# MCU_and_Antenna.net
KiCad netlist of a schematic drawn in Altium Designer
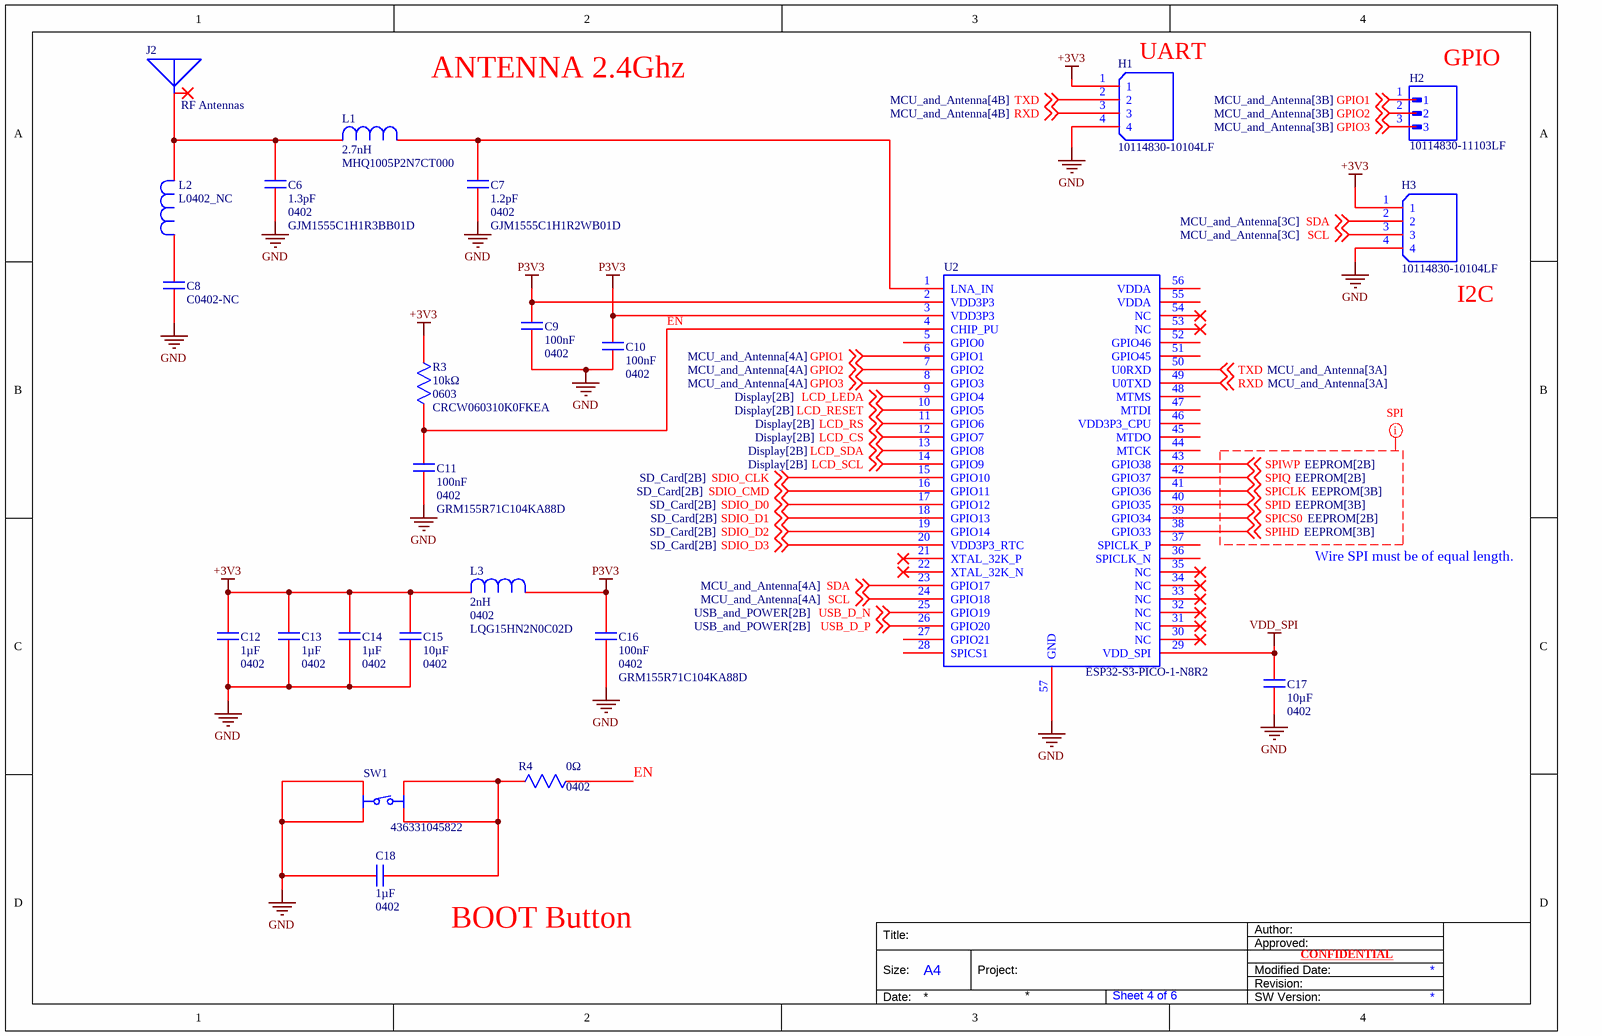
[diagram p0: MCU_and_Antenna.SchDoc]

(export (version "E")
  (design (tool "Eeschema 10.0.6"))
  (components
    (comp (ref "C6")
      (value "GJM1555C1H1R3BB01D")
      (footprint "CAPC1005X55N")
      (description "50V 1.3pF C0G 0402 Multilayer Ceramic Capacitors MLCC - SMD/SMT ROHS")
      (fields
        (field (name "MANUFACTURER") "Murata")
        (field (name "LCSC PART") "C161309")
        (field (name "CASE CODE (IMPERIAL)") "0402")
        (field (name "ALTIUM_VALUE") "1.3pF")
      )
      (libsource (lib "Schlib") (part "GJM1555C1H1R3BB01D"))
    )
    (comp (ref "C7")
      (value "GJM1555C1H1R2WB01D")
      (footprint "CAPC1005X55N")
      (description "50V 1.2pF C0G 0402 Multilayer Ceramic Capacitors MLCC - SMD/SMT ROHS")
      (fields
        (field (name "MANUFACTURER") "Murata")
        (field (name "VOLTAGE") "50V")
        (field (name "CASE/PACKAGE") "0402")
        (field (name "ALTIUM_VALUE") "1.2pF")
      )
      (libsource (lib "Schlib") (part "GJM1555C1H1R2WB01D"))
    )
    (comp (ref "C8")
      (value "C0402-NC")
      (footprint "CAPC1005X55N - NC")
      (libsource (lib "Schlib") (part "C0402-NC"))
    )
    (comp (ref "C9")
      (value "100nF")
      (footprint "CAPC1005X55N")
      (description "16V 100nF X7R ±10% 0402 Multilayer Ceramic Capacitors MLCC - SMD/SMT ROHS")
      (fields
        (field (name "MANUFACTURER") "Murata")
        (field (name "MANUFACTURER PART NUMBER") "GRM155R71C104KA88D")
        (field (name "CASE/PACKAGE") "0402")
      )
      (libsource (lib "Schlib") (part "GRM155R71C104KA88D"))
    )
    (comp (ref "C10")
      (value "100nF")
      (footprint "CAPC1005X55N")
      (description "16V 100nF X7R ±10% 0402 Multilayer Ceramic Capacitors MLCC - SMD/SMT ROHS")
      (fields
        (field (name "MANUFACTURER") "Murata")
        (field (name "MANUFACTURER PART NUMBER") "GRM155R71C104KA88D")
        (field (name "CASE/PACKAGE") "0402")
      )
      (libsource (lib "Schlib") (part "GRM155R71C104KA88D"))
    )
    (comp (ref "C11")
      (value "GRM155R71C104KA88D")
      (footprint "CAPC1005X55N")
      (description "16V 100nF X7R ±10% 0402 Multilayer Ceramic Capacitors MLCC - SMD/SMT ROHS")
      (fields
        (field (name "MANUFACTURER") "Murata")
        (field (name "TOLERANCE") "10%")
        (field (name "CASE/PACKAGE") "0402")
        (field (name "ALTIUM_VALUE") "100nF")
      )
      (libsource (lib "Schlib") (part "GRM155R71C104KA88D"))
    )
    (comp (ref "C12")
      (value "1µF")
      (footprint "CAPC1005X55N")
      (description "10V 1uF X5R 卤10% 0402 Multilayer Ceramic Capacitors MLCC - SMD/SMT ROHS")
      (fields
        (field (name "MANUFACTURER") "Samsung Electro-Mechanics")
        (field (name "MANUFACTURER PART NUMBER") "CL05A105KP5NNNC")
        (field (name "CASE/PACKAGE") "0402")
      )
      (libsource (lib "Schlib") (part "CL05A105KP5NNNC"))
    )
    (comp (ref "C13")
      (value "1µF")
      (footprint "CAPC1005X55N")
      (description "10V 1uF X5R 卤10% 0402 Multilayer Ceramic Capacitors MLCC - SMD/SMT ROHS")
      (fields
        (field (name "MANUFACTURER") "Samsung Electro-Mechanics")
        (field (name "MANUFACTURER PART NUMBER") "CL05A105KP5NNNC")
        (field (name "CASE/PACKAGE") "0402")
      )
      (libsource (lib "Schlib") (part "CL05A105KP5NNNC"))
    )
    (comp (ref "C14")
      (value "1µF")
      (footprint "CAPC1005X55N")
      (description "10V 1uF X5R 卤10% 0402 Multilayer Ceramic Capacitors MLCC - SMD/SMT ROHS")
      (fields
        (field (name "MANUFACTURER") "Samsung Electro-Mechanics")
        (field (name "MANUFACTURER PART NUMBER") "CL05A105KP5NNNC")
        (field (name "CASE/PACKAGE") "0402")
      )
      (libsource (lib "Schlib") (part "CL05A105KP5NNNC"))
    )
    (comp (ref "C15")
      (value "10µF")
      (footprint "CAPC1005X55N")
      (description "6.3V 10uF X5R ±20% 0402 Multilayer Ceramic Capacitors MLCC - SMD/SMT ROHS")
      (fields
        (field (name "MANUFACTURER") "Murata")
        (field (name "MANUFACTURER PART NUMBER") "GRM155R60J106ME15D")
        (field (name "CASE/PACKAGE") "0402")
      )
      (libsource (lib "Schlib") (part "GRM155R60J106ME15D"))
    )
    (comp (ref "C16")
      (value "GRM155R71C104KA88D")
      (footprint "CAPC1005X55N")
      (description "16V 100nF X7R ±10% 0402 Multilayer Ceramic Capacitors MLCC - SMD/SMT ROHS")
      (fields
        (field (name "MANUFACTURER") "Murata")
        (field (name "TOLERANCE") "10%")
        (field (name "CASE/PACKAGE") "0402")
        (field (name "ALTIUM_VALUE") "100nF")
      )
      (libsource (lib "Schlib") (part "GRM155R71C104KA88D"))
    )
    (comp (ref "C17")
      (value "10µF")
      (footprint "CAPC1005X55N")
      (description "6.3V 10uF X5R ±20% 0402 Multilayer Ceramic Capacitors MLCC - SMD/SMT ROHS")
      (fields
        (field (name "MANUFACTURER") "Murata")
        (field (name "MANUFACTURER PART NUMBER") "GRM155R60J106ME15D")
        (field (name "CASE/PACKAGE") "0402")
      )
      (libsource (lib "Schlib") (part "GRM155R60J106ME15D"))
    )
    (comp (ref "C18")
      (value "1µF")
      (footprint "CAPC1005X55N")
      (description "10V 1uF X5R 卤10% 0402 Multilayer Ceramic Capacitors MLCC - SMD/SMT ROHS")
      (fields
        (field (name "MANUFACTURER") "Samsung Electro-Mechanics")
        (field (name "MANUFACTURER PART NUMBER") "CL05A105KP5NNNC")
        (field (name "CASE/PACKAGE") "0402")
      )
      (libsource (lib "Schlib") (part "CL05A105KP5NNNC"))
    )
    (comp (ref "H1")
      (value "10114830-10104LF")
      (footprint "AMPHENOL_10114830-10104LF")
      (description "Board Connector, 4 Contact(S), 1 Row(S), Male, Right Angle, 0.049 Inch Pitch, Surface Mount")
      (fields
        (field (name "MANUFACTURER") "Amphenol Communications Solutions")
        (field (name "LCSC PART") "C5407185")
      )
      (libsource (lib "Schlib") (part "10114830-10104LF"))
    )
    (comp (ref "H2")
      (value "10114830-11103LF")
      (footprint "AMPHENOL_10114830-11103LF")
      (description "WTB 1.25 WAFER 90 SMT-10114830-11103LF ¦ Amphenol FCI (Amphenol CS) 1011483011103LF")
      (fields
        (field (name "MANUFACTURER") "Amphenol Communications Solutions")
        (field (name "LCSC PART") "C5407064")
      )
      (libsource (lib "Schlib") (part "10114830-11103LF"))
    )
    (comp (ref "H3")
      (value "10114830-10104LF")
      (footprint "AMPHENOL_10114830-10104LF")
      (description "Board Connector, 4 Contact(S), 1 Row(S), Male, Right Angle, 0.049 Inch Pitch, Surface Mount")
      (fields
        (field (name "MANUFACTURER") "Amphenol Communications Solutions")
        (field (name "LCSC PART") "C5407185")
      )
      (libsource (lib "Schlib") (part "10114830-10104LF"))
    )
    (comp (ref "J2")
      (value "RF Antennas")
      (footprint "ANT3216LL00R2400A")
      (description "CERAMIC HELIX CHIP ANTENNA, 433MHZ, 1204; Available until stocks are exhausted")
      (fields
        (field (name "MANUFACTURER") "Yageo Group")
        (field (name "MANUFACTURER PART NUMBER") "ANT3216LL00R2400A")
      )
      (libsource (lib "Schlib") (part "ANT3216LL00R2400A"))
    )
    (comp (ref "L1")
      (value "MHQ1005P2N7CT000")
      (footprint "IND_1005_TDK")
      (description "General Purpose Inductor, 0.0027uH, 7.4074%, 1 Element, Ceramic-Core, SMD, 0402")
      (fields
        (field (name "MANUFACTURER") "TDK")
        (field (name "TOLERANCE") "0.07%")
        (field (name "ALTIUM_VALUE") "2.7nH")
      )
      (libsource (lib "Schlib") (part "MHQ1005P2N7CT000"))
    )
    (comp (ref "L2")
      (value "L0402_NC")
      (footprint "IND_1005_TDK_NC")
      (libsource (lib "Schlib") (part "L0402_NC"))
    )
    (comp (ref "L3")
      (value "LQG15HN2N0C02D")
      (footprint "INDC1005X55N")
      (description "General Purpose Inductor, 0.002uH, 10%, 1 Element, Reflow soldering, 1005/0402")
      (fields
        (field (name "MANUFACTURER") "Murata")
        (field (name "TOLERANCE") "10%")
        (field (name "CASE/PACKAGE") "0402")
        (field (name "ALTIUM_VALUE") "2nH")
      )
      (libsource (lib "Schlib") (part "LQG15HN2N0C02D"))
    )
    (comp (ref "R3")
      (value "CRCW060310K0FKEA")
      (footprint "RES_CRCW_0603")
      (description "Fixed Resistor, Metal Glaze/Thick Film, 0.1W, 10000ohm, 75V, 1% +/-Tol, Surface Mount, 0603")
      (fields
        (field (name "MANUFACTURER") "Vishay")
        (field (name "TOLERANCE") "1%")
        (field (name "CASE CODE (IMPERIAL)") "0603")
        (field (name "ALTIUM_VALUE") "10kΩ")
      )
      (libsource (lib "Schlib") (part "CRCW060310K0FKEA"))
    )
    (comp (ref "R4")
      (value "0Ω")
      (footprint "RC0402N_YAG-M")
      (description "GENERAL PURPOSE CHIP RESISTOR Metal Glaze/thick Film, 0.0625W, 0ohm, Surface Mount, 0402")
      (fields
        (field (name "MANUFACTURER") "Yageo Group")
        (field (name "MANUFACTURER PART NUMBER") "RC0402JR-070RL")
        (field (name "CASE/PACKAGE") "0402")
      )
      (libsource (lib "Schlib") (part "RC0402JR-070RL"))
    )
    (comp (ref "SW1")
      (value "436331045822")
      (footprint "436331045822")
      (description "Wurth Elektronik tactile switch, Solder terminal, size 4.5 x 4.7mm, surface, SPST")
      (fields (field (name "MANUFACTURER") "Wurth Elektronik") (field (name "LCSC PART") "C5143619"))
      (libsource (lib "Schlib") (part "436331045822"))
    )
    (comp (ref "U2")
      (value "ESP32-S3-PICO-1-N8R2")
      (footprint "QFN56_7X7_EXP-L")
      (description "ESP32-S3-PICO-1 Is A System-in-p")
      (fields (field (name "MANUFACTURER") "Espressif Systems"))
      (libsource (lib "Schlib") (part "ESP32-S3-PICO-1-N8R2"))
    )
  )
  (nets
    (net (code "1") (name "+3V3") (class "Default")
      (node (ref "C12") (pin "2") (pinfunction "2_2") (pintype "passive"))
      (node (ref "C13") (pin "2") (pinfunction "2_2") (pintype "passive"))
      (node (ref "C14") (pin "2") (pinfunction "2_2") (pintype "passive"))
      (node (ref "C15") (pin "2") (pinfunction "2_2") (pintype "passive"))
      (node (ref "H1") (pin "1") (pinfunction "1_1") (pintype "passive"))
      (node (ref "H3") (pin "1") (pinfunction "1_1") (pintype "passive"))
      (node (ref "L3") (pin "2") (pinfunction "2_2") (pintype "passive"))
      (node (ref "R3") (pin "1") (pinfunction "1_1") (pintype "passive"))
    )
    (net (code "2") (name "/EN") (class "Default")
      (node (ref "C11") (pin "1") (pinfunction "1_1") (pintype "passive"))
      (node (ref "R3") (pin "2") (pinfunction "2_2") (pintype "passive"))
      (node (ref "R4") (pin "2") (pinfunction "2_2") (pintype "passive"))
      (node (ref "U2") (pin "4") (pinfunction "CHIP_PU_4") (pintype "passive"))
    )
    (net (code "3") (name "GND") (class "Default")
      (node (ref "C10") (pin "2") (pinfunction "2_2") (pintype "passive"))
      (node (ref "C11") (pin "2") (pinfunction "2_2") (pintype "passive"))
      (node (ref "C12") (pin "1") (pinfunction "1_1") (pintype "passive"))
      (node (ref "C13") (pin "1") (pinfunction "1_1") (pintype "passive"))
      (node (ref "C14") (pin "1") (pinfunction "1_1") (pintype "passive"))
      (node (ref "C15") (pin "1") (pinfunction "1_1") (pintype "passive"))
      (node (ref "C16") (pin "2") (pinfunction "2_2") (pintype "passive"))
      (node (ref "C17") (pin "1") (pinfunction "1_1") (pintype "passive"))
      (node (ref "C18") (pin "2") (pinfunction "2_2") (pintype "passive"))
      (node (ref "C6") (pin "1") (pinfunction "1_1") (pintype "passive"))
      (node (ref "C7") (pin "1") (pinfunction "1_1") (pintype "passive"))
      (node (ref "C8") (pin "1") (pinfunction "1_1") (pintype "passive"))
      (node (ref "C9") (pin "2") (pinfunction "2_2") (pintype "passive"))
      (node (ref "H1") (pin "4") (pinfunction "4_4") (pintype "passive"))
      (node (ref "H3") (pin "4") (pinfunction "4_4") (pintype "passive"))
      (node (ref "SW1") (pin "1") (pinfunction "3_1") (pintype "passive"))
      (node (ref "SW1") (pin "3") (pinfunction "1_3") (pintype "passive"))
      (node (ref "U2") (pin "57") (pinfunction "GND_57") (pintype "power_in"))
    )
    (net (code "4") (name "GPIO1") (class "Default")
      (node (ref "H2") (pin "1") (pinfunction "1_1") (pintype "passive"))
      (node (ref "U2") (pin "6") (pinfunction "GPIO1_6") (pintype "passive"))
    )
    (net (code "5") (name "GPIO2") (class "Default")
      (node (ref "H2") (pin "2") (pinfunction "2_2") (pintype "passive"))
      (node (ref "U2") (pin "7") (pinfunction "GPIO2_7") (pintype "passive"))
    )
    (net (code "6") (name "GPIO3") (class "Default")
      (node (ref "H2") (pin "3") (pinfunction "3_3") (pintype "passive"))
      (node (ref "U2") (pin "8") (pinfunction "GPIO3_8") (pintype "passive"))
    )
    (net (code "7") (name "LCD_CS") (class "Default")
      (node (ref "U2") (pin "12") (pinfunction "GPIO7_12") (pintype "passive"))
    )
    (net (code "8") (name "LCD_LEDA") (class "Default")
      (node (ref "U2") (pin "9") (pinfunction "GPIO4_9") (pintype "passive"))
    )
    (net (code "9") (name "LCD_RESET") (class "Default")
      (node (ref "U2") (pin "10") (pinfunction "GPIO5_10") (pintype "passive"))
    )
    (net (code "10") (name "LCD_RS") (class "Default")
      (node (ref "U2") (pin "11") (pinfunction "GPIO6_11") (pintype "passive"))
    )
    (net (code "11") (name "LCD_SCL") (class "Default")
      (node (ref "U2") (pin "14") (pinfunction "GPIO9_14") (pintype "passive"))
    )
    (net (code "12") (name "LCD_SDA") (class "Default")
      (node (ref "U2") (pin "13") (pinfunction "GPIO8_13") (pintype "passive"))
    )
    (net (code "13") (name "Net-(C6-Pad2)") (class "Default")
      (node (ref "C6") (pin "2") (pinfunction "2_2") (pintype "passive"))
      (node (ref "J2") (pin "1") (pinfunction "1_1") (pintype "passive"))
      (node (ref "L1") (pin "2") (pinfunction "2_2") (pintype "passive"))
      (node (ref "L2") (pin "1") (pinfunction "1_1") (pintype "passive"))
    )
    (net (code "14") (name "Net-(C8-Pad2)") (class "Default")
      (node (ref "C8") (pin "2") (pinfunction "2_2") (pintype "passive"))
      (node (ref "L2") (pin "2") (pinfunction "2_2") (pintype "passive"))
    )
    (net (code "15") (name "Net-(SW1-2)") (class "Default")
      (node (ref "C18") (pin "1") (pinfunction "1_1") (pintype "passive"))
      (node (ref "R4") (pin "1") (pinfunction "1_1") (pintype "passive"))
      (node (ref "SW1") (pin "2") (pinfunction "4_2") (pintype "passive"))
      (node (ref "SW1") (pin "4") (pinfunction "2_4") (pintype "passive"))
    )
    (net (code "16") (name "Net-(U2-LNA_IN)") (class "Default")
      (node (ref "C7") (pin "2") (pinfunction "2_2") (pintype "passive"))
      (node (ref "L1") (pin "1") (pinfunction "1_1") (pintype "passive"))
      (node (ref "U2") (pin "1") (pinfunction "LNA_IN_1") (pintype "passive"))
    )
    (net (code "17") (name "P3V3") (class "Default")
      (node (ref "C10") (pin "1") (pinfunction "1_1") (pintype "passive"))
      (node (ref "C16") (pin "1") (pinfunction "1_1") (pintype "passive"))
      (node (ref "C9") (pin "1") (pinfunction "1_1") (pintype "passive"))
      (node (ref "L3") (pin "1") (pinfunction "1_1") (pintype "passive"))
      (node (ref "U2") (pin "2") (pinfunction "VDD3P3_2") (pintype "power_in"))
      (node (ref "U2") (pin "3") (pinfunction "VDD3P3_3") (pintype "power_in"))
    )
    (net (code "18") (name "RXD") (class "Default")
      (node (ref "H1") (pin "3") (pinfunction "3_3") (pintype "passive"))
      (node (ref "U2") (pin "49") (pinfunction "U0TXD_49") (pintype "passive"))
    )
    (net (code "19") (name "SCL") (class "Default")
      (node (ref "H3") (pin "3") (pinfunction "3_3") (pintype "passive"))
      (node (ref "U2") (pin "24") (pinfunction "GPIO18_24") (pintype "passive"))
    )
    (net (code "20") (name "SDA") (class "Default")
      (node (ref "H3") (pin "2") (pinfunction "2_2") (pintype "passive"))
      (node (ref "U2") (pin "23") (pinfunction "GPIO17_23") (pintype "passive"))
    )
    (net (code "21") (name "SDIO_CLK") (class "Default")
      (node (ref "U2") (pin "15") (pinfunction "GPIO10_15") (pintype "passive"))
    )
    (net (code "22") (name "SDIO_CMD") (class "Default")
      (node (ref "U2") (pin "16") (pinfunction "GPIO11_16") (pintype "passive"))
    )
    (net (code "23") (name "SDIO_D0") (class "Default")
      (node (ref "U2") (pin "17") (pinfunction "GPIO12_17") (pintype "passive"))
    )
    (net (code "24") (name "SDIO_D1") (class "Default")
      (node (ref "U2") (pin "18") (pinfunction "GPIO13_18") (pintype "passive"))
    )
    (net (code "25") (name "SDIO_D2") (class "Default")
      (node (ref "U2") (pin "19") (pinfunction "GPIO14_19") (pintype "passive"))
    )
    (net (code "26") (name "SDIO_D3") (class "Default")
      (node (ref "U2") (pin "20") (pinfunction "VDD3P3_RTC_20") (pintype "power_in"))
    )
    (net (code "27") (name "SPICLK") (class "Default")
      (node (ref "U2") (pin "41") (pinfunction "GPIO36_41") (pintype "passive"))
    )
    (net (code "28") (name "SPICS0") (class "Default")
      (node (ref "U2") (pin "39") (pinfunction "GPIO34_39") (pintype "passive"))
    )
    (net (code "29") (name "SPID") (class "Default")
      (node (ref "U2") (pin "40") (pinfunction "GPIO35_40") (pintype "passive"))
    )
    (net (code "30") (name "SPIHD") (class "Default")
      (node (ref "U2") (pin "38") (pinfunction "GPIO33_38") (pintype "passive"))
    )
    (net (code "31") (name "SPIQ") (class "Default")
      (node (ref "U2") (pin "42") (pinfunction "GPIO37_42") (pintype "passive"))
    )
    (net (code "32") (name "SPIWP") (class "Default")
      (node (ref "U2") (pin "43") (pinfunction "GPIO38_43") (pintype "passive"))
    )
    (net (code "33") (name "TXD") (class "Default")
      (node (ref "H1") (pin "2") (pinfunction "2_2") (pintype "passive"))
      (node (ref "U2") (pin "50") (pinfunction "U0RXD_50") (pintype "passive"))
    )
    (net (code "34") (name "USB_D_N") (class "Default")
      (node (ref "U2") (pin "25") (pinfunction "GPIO19_25") (pintype "passive"))
    )
    (net (code "35") (name "USB_D_P") (class "Default")
      (node (ref "U2") (pin "26") (pinfunction "GPIO20_26") (pintype "passive"))
    )
    (net (code "36") (name "VDD_SPI") (class "Default")
      (node (ref "C17") (pin "2") (pinfunction "2_2") (pintype "passive"))
      (node (ref "U2") (pin "29") (pinfunction "VDD_SPI_29") (pintype "power_in"))
    )
    (net (code "37") (name "unconnected-(J2-Pad2)") (class "Default")
      (node (ref "J2") (pin "2") (pinfunction "2_2") (pintype "passive+no_connect"))
    )
    (net (code "38") (name "unconnected-(U2-GPIO0-Pad5)") (class "Default")
      (node (ref "U2") (pin "5") (pinfunction "GPIO0_5") (pintype "passive"))
    )
    (net (code "39") (name "unconnected-(U2-GPIO21-Pad27)") (class "Default")
      (node (ref "U2") (pin "27") (pinfunction "GPIO21_27") (pintype "passive"))
    )
    (net (code "40") (name "unconnected-(U2-GPIO45-Pad51)") (class "Default")
      (node (ref "U2") (pin "51") (pinfunction "GPIO45_51") (pintype "passive"))
    )
    (net (code "41") (name "unconnected-(U2-GPIO46-Pad52)") (class "Default")
      (node (ref "U2") (pin "52") (pinfunction "GPIO46_52") (pintype "passive"))
    )
    (net (code "42") (name "unconnected-(U2-MTCK-Pad44)") (class "Default")
      (node (ref "U2") (pin "44") (pinfunction "MTCK_44") (pintype "passive"))
    )
    (net (code "43") (name "unconnected-(U2-MTDI-Pad47)") (class "Default")
      (node (ref "U2") (pin "47") (pinfunction "MTDI_47") (pintype "passive"))
    )
    (net (code "44") (name "unconnected-(U2-MTDO-Pad45)") (class "Default")
      (node (ref "U2") (pin "45") (pinfunction "MTDO_45") (pintype "passive"))
    )
    (net (code "45") (name "unconnected-(U2-MTMS-Pad48)") (class "Default")
      (node (ref "U2") (pin "48") (pinfunction "MTMS_48") (pintype "passive"))
    )
    (net (code "46") (name "unconnected-(U2-NC-Pad30)") (class "Default")
      (node (ref "U2") (pin "30") (pinfunction "NC_30") (pintype "passive+no_connect"))
    )
    (net (code "47") (name "unconnected-(U2-NC-Pad31)") (class "Default")
      (node (ref "U2") (pin "31") (pinfunction "NC_31") (pintype "passive+no_connect"))
    )
    (net (code "48") (name "unconnected-(U2-NC-Pad32)") (class "Default")
      (node (ref "U2") (pin "32") (pinfunction "NC_32") (pintype "passive+no_connect"))
    )
    (net (code "49") (name "unconnected-(U2-NC-Pad33)") (class "Default")
      (node (ref "U2") (pin "33") (pinfunction "NC_33") (pintype "passive+no_connect"))
    )
    (net (code "50") (name "unconnected-(U2-NC-Pad34)") (class "Default")
      (node (ref "U2") (pin "34") (pinfunction "NC_34") (pintype "passive+no_connect"))
    )
    (net (code "51") (name "unconnected-(U2-NC-Pad35)") (class "Default")
      (node (ref "U2") (pin "35") (pinfunction "NC_35") (pintype "passive+no_connect"))
    )
    (net (code "52") (name "unconnected-(U2-NC-Pad53)") (class "Default")
      (node (ref "U2") (pin "53") (pinfunction "NC_53") (pintype "passive+no_connect"))
    )
    (net (code "53") (name "unconnected-(U2-NC-Pad54)") (class "Default")
      (node (ref "U2") (pin "54") (pinfunction "NC_54") (pintype "passive+no_connect"))
    )
    (net (code "54") (name "unconnected-(U2-SPICLK_N-Pad36)") (class "Default")
      (node (ref "U2") (pin "36") (pinfunction "SPICLK_N_36") (pintype "passive"))
    )
    (net (code "55") (name "unconnected-(U2-SPICLK_P-Pad37)") (class "Default")
      (node (ref "U2") (pin "37") (pinfunction "SPICLK_P_37") (pintype "passive"))
    )
    (net (code "56") (name "unconnected-(U2-SPICS1-Pad28)") (class "Default")
      (node (ref "U2") (pin "28") (pinfunction "SPICS1_28") (pintype "passive"))
    )
    (net (code "57") (name "unconnected-(U2-VDD3P3_CPU-Pad46)") (class "Default")
      (node (ref "U2") (pin "46") (pinfunction "VDD3P3_CPU_46") (pintype "power_in"))
    )
    (net (code "58") (name "unconnected-(U2-VDDA-Pad55)") (class "Default")
      (node (ref "U2") (pin "55") (pinfunction "VDDA_55") (pintype "power_in"))
    )
    (net (code "59") (name "unconnected-(U2-VDDA-Pad56)") (class "Default")
      (node (ref "U2") (pin "56") (pinfunction "VDDA_56") (pintype "power_in"))
    )
    (net (code "60") (name "unconnected-(U2-XTAL_32K_N-Pad22)") (class "Default")
      (node (ref "U2") (pin "22") (pinfunction "XTAL_32K_N_22") (pintype "passive+no_connect"))
    )
    (net (code "61") (name "unconnected-(U2-XTAL_32K_P-Pad21)") (class "Default")
      (node (ref "U2") (pin "21") (pinfunction "XTAL_32K_P_21") (pintype "passive+no_connect"))
    )
  )
)
